# LM2596_Ayarlanabilir_Buck_Converter_emat.net
KiCad netlist of a schematic drawn in Altium Designer
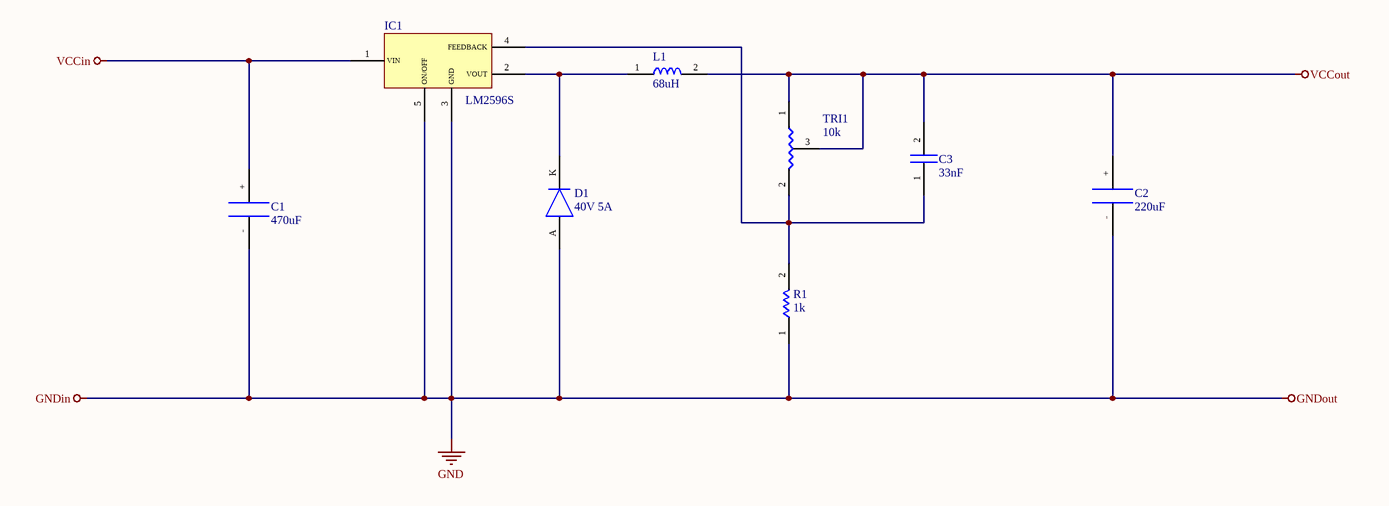
[diagram p0: LM2596 Ayarlanabilir Buck Converter Şematik.SchDoc]

(export (version "E")
  (design (tool "Eeschema 10.0.6"))
  (components
    (comp (ref "C1")
      (value "470uF")
      (footprint "470uF 50V Elektrolikit Kapasitör")
      (libsource (lib "470uF 50V Elektrolikit Kapasitör") (part "470uF 50V Elektrolikit Kapasitör"))
    )
    (comp (ref "C2")
      (value "220uF")
      (footprint "220uF 35V Elektrolikit Kapasitör")
      (libsource (lib "220uF 35V Elektrolikit Kapasitör") (part "220uF 35V Elektrolikit Kapasitör"))
    )
    (comp (ref "C3")
      (value "33nF")
      (footprint "33nF Kapasitör")
      (libsource (lib "33nF Kapasitör") (part "33nF Kapasitör"))
    )
    (comp (ref "D1")
      (value "40V 5A")
      (footprint "40V 5A Schottky Diyot")
      (libsource (lib "40V 5A Schottky Diyot") (part "40V 5A Schottky Diyot"))
    )
    (comp (ref "IC1") (value "LM2596S") (footprint "LM2596S") (libsource (lib "LM2596S") (part "LM2596S")))
    (comp (ref "L1")
      (value "68uH")
      (footprint "68uH İndüktör")
      (libsource (lib "68uH İndüktör") (part "68uH İndüktör"))
    )
    (comp (ref "R1")
      (value "1k")
      (footprint "10k SMD Direnç")
      (libsource (lib "10k SMD Direnç") (part "10k SMD Direnç"))
    )
    (comp (ref "TRI1")
      (value "10k")
      (footprint "Düzenleyici Potansiyometre")
      (libsource (lib "Düzenleyici Potansiyometre") (part "Düzenleyici Potansiyometre"))
    )
  )
  (nets
    (net (code "1") (name "GND") (class "Default")
      (node (ref "C1") (pin "-") (pintype "passive"))
      (node (ref "C2") (pin "-") (pintype "passive"))
      (node (ref "D1") (pin "A") (pintype "passive"))
      (node (ref "IC1") (pin "3") (pinfunction "GND_3") (pintype "passive"))
      (node (ref "IC1") (pin "5") (pinfunction "ON/OFF_5") (pintype "passive"))
      (node (ref "R1") (pin "1") (pintype "passive"))
    )
    (net (code "2") (name "Net-(IC1-FEEDBACK)") (class "Default")
      (node (ref "C3") (pin "1") (pintype "passive"))
      (node (ref "IC1") (pin "4") (pinfunction "FEEDBACK_4") (pintype "passive"))
      (node (ref "R1") (pin "2") (pintype "passive"))
      (node (ref "TRI1") (pin "2") (pintype "passive"))
    )
    (net (code "3") (name "Net-(IC1-VOUT)") (class "Default")
      (node (ref "D1") (pin "K") (pintype "passive"))
      (node (ref "IC1") (pin "2") (pinfunction "VOUT_2") (pintype "passive"))
      (node (ref "L1") (pin "1") (pintype "passive"))
    )
    (net (code "4") (name "VCCin") (class "Default")
      (node (ref "C1") (pin "+") (pintype "passive"))
      (node (ref "IC1") (pin "1") (pinfunction "VIN_1") (pintype "passive"))
    )
    (net (code "5") (name "VCCout") (class "Default")
      (node (ref "C2") (pin "+") (pintype "passive"))
      (node (ref "C3") (pin "2") (pintype "passive"))
      (node (ref "L1") (pin "2") (pintype "passive"))
      (node (ref "TRI1") (pin "1") (pintype "passive"))
      (node (ref "TRI1") (pin "3") (pintype "passive"))
    )
  )
)
